# Sheet1.net
KiCad netlist of a schematic drawn in Altium Designer
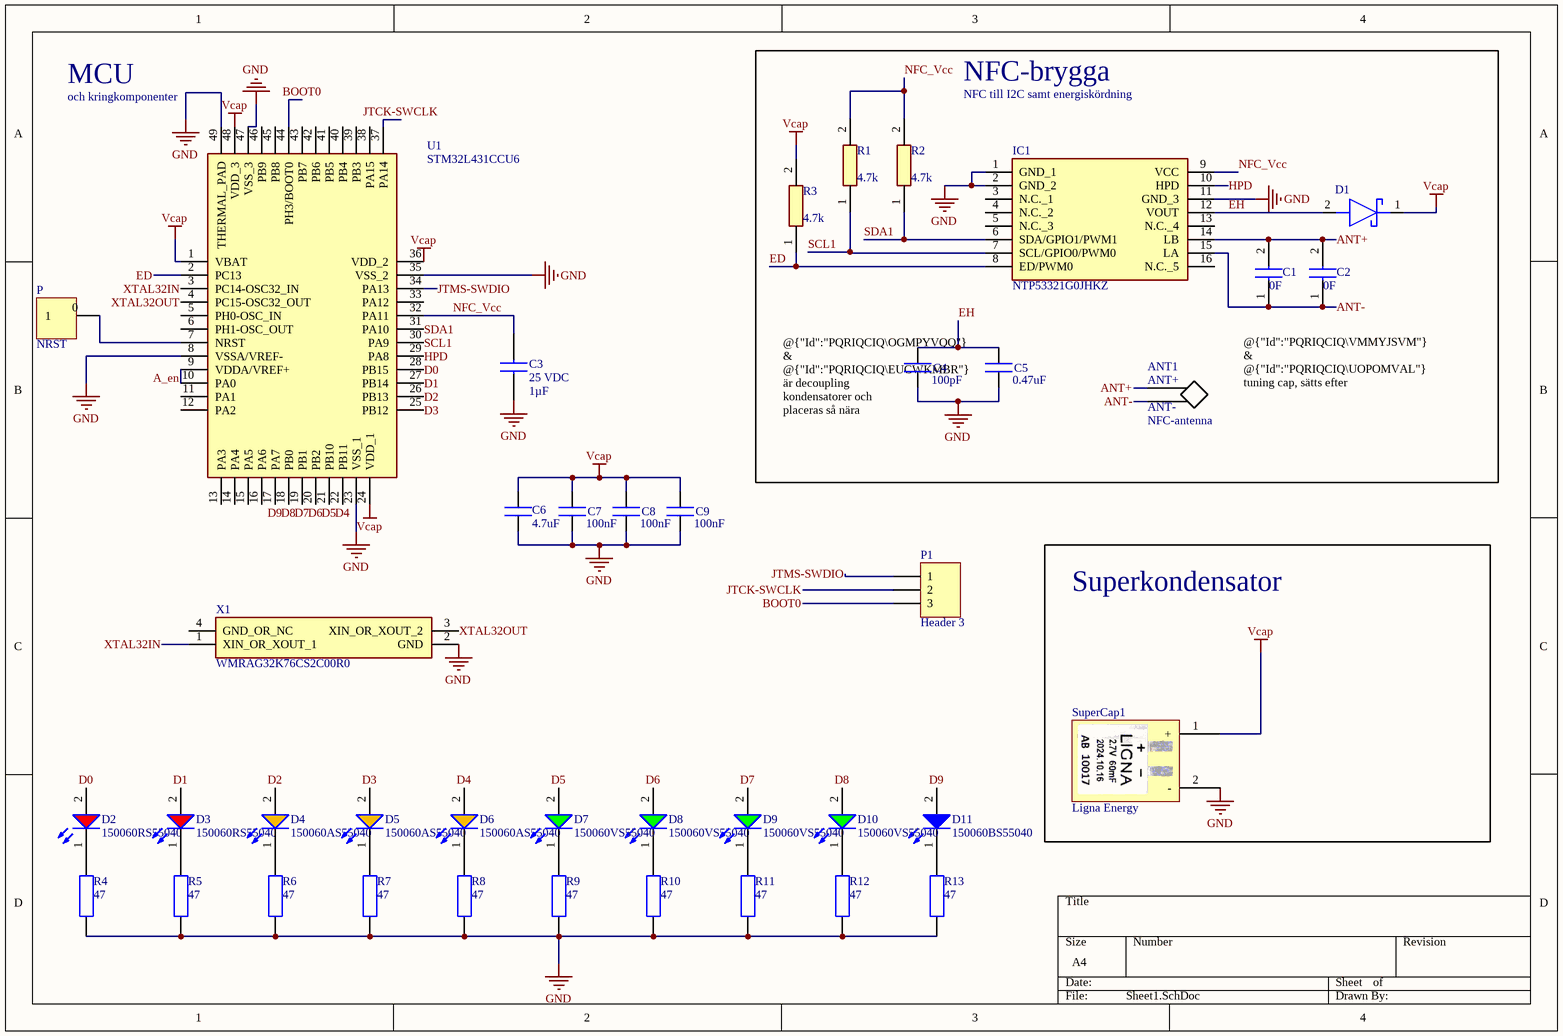
[diagram p0: Sheet1.SchDoc]

(export (version "E")
  (design (tool "Eeschema 10.0.6"))
  (components
    (comp (ref "ANT1")
      (value "NFC-antenna")
      (footprint "antenna3")
      (libsource (lib "Schlib") (part "NFC-antenna"))
    )
    (comp (ref "C1")
      (value "0F")
      (footprint "CAPC1005X70N")
      (description "Multilayer Ceramic Capacitors MLCC - SMD/SMT")
      (fields
        (field (name "MOUSER PART NUMBER") "81-GRM155C81C474KE1D")
        (field (name "MANUFACTURER_PART_NUMBER") "GRM155C81C474KE01D")
      )
      (libsource (lib "Linköpings Universitet (SE)") (part "GRM155C81C474KE01D"))
    )
    (comp (ref "C2")
      (value "0F")
      (footprint "CAPC1005X70N")
      (description "Multilayer Ceramic Capacitors MLCC - SMD/SMT")
      (fields
        (field (name "MOUSER PART NUMBER") "81-GRM155C81C474KE1D")
        (field (name "MANUFACTURER_PART_NUMBER") "GRM155C81C474KE01D")
      )
      (libsource (lib "Linköpings Universitet (SE)") (part "GRM155C81C474KE01D"))
    )
    (comp (ref "C3")
      (value "1µF")
      (footprint "CAPC1005X55N")
      (description "Capacitor")
      (fields
        (field (name "RATED VOLTAGE") "25 VDC")
        (field (name "MOUSER PART NUMBER") "81-GRM155R61E105KA2D")
        (field (name "ARROW PART NUMBER") "GRM155R61E105KA12D")
      )
      (libsource (lib "Linköpings Universitet (SE)") (part "GRM155R61E105KA12D"))
    )
    (comp (ref "C4")
      (value "C0402C101KCGACAUTO")
      (footprint "CAPC1005X70N")
      (description "Multilayer Ceramic Capacitors MLCC - SMD/SMT 500V 0.0001uF C0G 0402 10% AEC-Q200")
      (fields (field (name "CAPACITANCE") "100pF"))
      (libsource (lib "Schlib") (part "Generic capacitor"))
    )
    (comp (ref "C5")
      (value "C0402C101KCMBASJ105SB7474KFNA01GACAUTO")
      (footprint "CAPC1005X70N")
      (description "Multilayer Ceramic Capacitors MLCC - SMD/SMT 500V 0.0001uF C0G 0402 10% AEC-Q200")
      (fields (field (name "CAPACITANCE") "0.47uF"))
      (libsource (lib "Schlib") (part "Generic capacitor"))
    )
    (comp (ref "C6")
      (value "C0402C475K8PACTU")
      (footprint "CAPC1005X70N")
      (description "Multilayer Ceramic Capacitors MLCC - SMD/SMT")
      (fields (field (name "CAPACITANCE") "4.7uF"))
      (libsource (lib "Schlib") (part "Generic capacitor"))
    )
    (comp (ref "C7")
      (value "MLAST105SB5104KFNA01")
      (footprint "CAPC1005X70N")
      (description "Multilayer Ceramic Capacitors MLCC - SMD/SMT 25V 0.1uF X5R 0402 10% Medical")
      (fields (field (name "CAPACITANCE") "100nF"))
      (libsource (lib "Schlib") (part "Generic capacitor"))
    )
    (comp (ref "C8")
      (value "MLAST105SB5104KFNA01")
      (footprint "CAPC1005X70N")
      (description "Multilayer Ceramic Capacitors MLCC - SMD/SMT 25V 0.1uF X5R 0402 10% Medical")
      (fields (field (name "CAPACITANCE") "100nF"))
      (libsource (lib "Schlib") (part "Generic capacitor"))
    )
    (comp (ref "C9")
      (value "MLAST105SB5104KFNA01")
      (footprint "CAPC1005X70N")
      (description "Multilayer Ceramic Capacitors MLCC - SMD/SMT 25V 0.1uF X5R 0402 10% Medical")
      (fields (field (name "CAPACITANCE") "100nF"))
      (libsource (lib "Schlib") (part "Generic capacitor"))
    )
    (comp (ref "D1")
      (value "RBE01VYM6AFHTR")
      (footprint "RBE01VYM6AFHTR")
      (description "DIODE SCHOTTKY 6V 100MA TUMD2M")
      (fields (field (name "MOUSER PART NUMBER") "755-RBE01VYM6AFHTR"))
      (libsource (lib "Linköpings Universitet (SE)") (part "RBE01VYM6AFHTR"))
    )
    (comp (ref "D2")
      (value "150060RS55040")
      (footprint "WL-SMCD_0603")
      (description "LED RED DIFFUSED 0603 SMD")
      (libsource (lib "Altium Content Vault") (part "LED_Red_2A-1K"))
    )
    (comp (ref "D3")
      (value "150060RS55040")
      (footprint "WL-SMCD_0603")
      (description "LED RED DIFFUSED 0603 SMD")
      (libsource (lib "Altium Content Vault") (part "LED_Red_2A-1K"))
    )
    (comp (ref "D4")
      (value "150060AS55040")
      (footprint "WL-SMCD_0603")
      (description "150060AS55040 WL-SMCD SMT Mono-color Chip LED Diffused")
      (libsource (lib "Altium Content Vault") (part "LED_Amber_2A-1K"))
    )
    (comp (ref "D5")
      (value "150060AS55040")
      (footprint "WL-SMCD_0603")
      (description "150060AS55040 WL-SMCD SMT Mono-color Chip LED Diffused")
      (libsource (lib "Altium Content Vault") (part "LED_Amber_2A-1K"))
    )
    (comp (ref "D6")
      (value "150060AS55040")
      (footprint "WL-SMCD_0603")
      (description "150060AS55040 WL-SMCD SMT Mono-color Chip LED Diffused")
      (libsource (lib "Altium Content Vault") (part "LED_Amber_2A-1K"))
    )
    (comp (ref "D7")
      (value "150060VS55040")
      (footprint "WL-SMCD_0603")
      (description "150060VS55040 WL-SMCD SMT Mono-color Chip LED Diffused")
      (libsource (lib "Altium Content Vault") (part "LED_Green_2A-1K"))
    )
    (comp (ref "D8")
      (value "150060VS55040")
      (footprint "WL-SMCD_0603")
      (description "150060VS55040 WL-SMCD SMT Mono-color Chip LED Diffused")
      (libsource (lib "Altium Content Vault") (part "LED_Green_2A-1K"))
    )
    (comp (ref "D9")
      (value "150060VS55040")
      (footprint "WL-SMCD_0603")
      (description "150060VS55040 WL-SMCD SMT Mono-color Chip LED Diffused")
      (libsource (lib "Altium Content Vault") (part "LED_Green_2A-1K"))
    )
    (comp (ref "D10")
      (value "150060VS55040")
      (footprint "WL-SMCD_0603")
      (description "150060VS55040 WL-SMCD SMT Mono-color Chip LED Diffused")
      (libsource (lib "Altium Content Vault") (part "LED_Green_2A-1K"))
    )
    (comp (ref "D11")
      (value "150060BS55040")
      (footprint "WL-SMCD_0603")
      (description "150060BS55040 WL-SMCD SMT Mono-color Chip LED Diffused")
      (libsource (lib "Altium Content Vault") (part "LED_Blue_2A-1K"))
    )
    (comp (ref "IC1")
      (value "NTP53321G0JHKZ")
      (footprint "NTP53321G0JHKZ")
      (description "Interface - Specialized NTAG")
      (fields (field (name "MOUSER PART NUMBER") "771-NTP53321G0JHKZ"))
      (libsource (lib "Linköpings Universitet (SE)") (part "NTP53321G0JHKZ"))
    )
    (comp (ref "P")
      (value "NRST")
      (footprint "Testupoint")
      (libsource (lib "Schlib") (part "testpointu desu"))
    )
    (comp (ref "P1")
      (value "Header 3")
      (footprint "HDR1X3")
      (description "Header, 3-Pin")
      (fields (field (name "PUBLISHER") "Altium Limited"))
      (libsource (lib "Linköpings Universitet (SE)") (part "Header 3H"))
    )
    (comp (ref "R1")
      (value "CRCW04024K70FKEDHP")
      (footprint "RESC1005X40N")
      (fields (field (name "MOUSER PART NUMBER") "71-CRCW04024K70FKEDH") (field (name "RESISTANCE") "4.7k"))
      (libsource (lib "Linköpings Universitet (SE)") (part "CRCW04024K70FKEDHP"))
    )
    (comp (ref "R2")
      (value "CRCW04024K70FKEDHP")
      (footprint "RESC1005X40N")
      (fields (field (name "MOUSER PART NUMBER") "71-CRCW04024K70FKEDH") (field (name "RESISTANCE") "4.7k"))
      (libsource (lib "Linköpings Universitet (SE)") (part "CRCW04024K70FKEDHP"))
    )
    (comp (ref "R3")
      (value "CRCW04024K70FKEDHP")
      (footprint "RESC1005X40N")
      (fields (field (name "MOUSER PART NUMBER") "71-CRCW04024K70FKEDH") (field (name "RESISTANCE") "4.7k"))
      (libsource (lib "Linköpings Universitet (SE)") (part "CRCW04024K70FKEDHP"))
    )
    (comp (ref "R4")
      (value "SFR01MZPJ470")
      (footprint "RESC1005X40N")
      (description "Thick Film Resistors Sulfur Tolerant Chip Resistors 0402 case size")
      (fields (field (name "RESISTANCE") "47"))
      (libsource (lib "") (part "Generic resistor_1"))
    )
    (comp (ref "R5")
      (value "SFR01MZPJ470")
      (footprint "RESC1005X40N")
      (description "Thick Film Resistors Sulfur Tolerant Chip Resistors 0402 case size")
      (fields (field (name "RESISTANCE") "47"))
      (libsource (lib "") (part "Generic resistor_1"))
    )
    (comp (ref "R6")
      (value "SFR01MZPJ470")
      (footprint "RESC1005X40N")
      (description "Thick Film Resistors Sulfur Tolerant Chip Resistors 0402 case size")
      (fields (field (name "RESISTANCE") "47"))
      (libsource (lib "Schlib") (part "Generic resistor"))
    )
    (comp (ref "R7")
      (value "SFR01MZPJ470")
      (footprint "RESC1005X40N")
      (description "Thick Film Resistors Sulfur Tolerant Chip Resistors 0402 case size")
      (fields (field (name "RESISTANCE") "47"))
      (libsource (lib "Schlib") (part "Generic resistor"))
    )
    (comp (ref "R8")
      (value "SFR01MZPJ470")
      (footprint "RESC1005X40N")
      (description "Thick Film Resistors Sulfur Tolerant Chip Resistors 0402 case size")
      (fields (field (name "RESISTANCE") "47"))
      (libsource (lib "Schlib") (part "Generic resistor"))
    )
    (comp (ref "R9")
      (value "SFR01MZPJ470")
      (footprint "RESC1005X40N")
      (description "Thick Film Resistors Sulfur Tolerant Chip Resistors 0402 case size")
      (fields (field (name "RESISTANCE") "47"))
      (libsource (lib "Schlib") (part "Generic resistor"))
    )
    (comp (ref "R10")
      (value "SFR01MZPJ470")
      (footprint "RESC1005X40N")
      (description "Thick Film Resistors Sulfur Tolerant Chip Resistors 0402 case size")
      (fields (field (name "RESISTANCE") "47"))
      (libsource (lib "Schlib") (part "Generic resistor"))
    )
    (comp (ref "R11")
      (value "SFR01MZPJ470")
      (footprint "RESC1005X40N")
      (description "Thick Film Resistors Sulfur Tolerant Chip Resistors 0402 case size")
      (fields (field (name "RESISTANCE") "47"))
      (libsource (lib "Schlib") (part "Generic resistor"))
    )
    (comp (ref "R12")
      (value "SFR01MZPJ470")
      (footprint "RESC1005X40N")
      (description "Thick Film Resistors Sulfur Tolerant Chip Resistors 0402 case size")
      (fields (field (name "RESISTANCE") "47"))
      (libsource (lib "Schlib") (part "Generic resistor"))
    )
    (comp (ref "R13")
      (value "SFR01MZPJ470")
      (footprint "RESC1005X40N")
      (description "Thick Film Resistors Sulfur Tolerant Chip Resistors 0402 case size")
      (fields (field (name "RESISTANCE") "47"))
      (libsource (lib "Schlib") (part "Generic resistor"))
    )
    (comp (ref "SuperCap1")
      (value "Ligna Energy")
      (footprint "S-Power 2R slim")
      (libsource (lib "Schlib") (part "S-Power 2R"))
    )
    (comp (ref "U1")
      (value "STM32L431CCU6")
      (footprint "QFN50P700X700X60-49N-D")
      (description "ARM Microcontrollers - MCU 16/32-BITS MICROS")
      (fields (field (name "MOUSER PART NUMBER") "511-STM32L431CCU6"))
      (libsource (lib "Linköpings Universitet (SE)") (part "STM32L431CCU6"))
    )
    (comp (ref "X1")
      (value "WMRAG32K76CS2C00R0")
      (footprint "WMRAG32K76CS2C00R0")
      (description "32.768 kHz +/-20ppm Crystal 8pF 75 kOhms 4-SMD")
      (fields (field (name "MOUSER PART NUMBER") "81-WMRAG32K76CS2C00R"))
      (libsource (lib "Linköpings Universitet (SE)") (part "WMRAG32K76CS2C00R0"))
    )
  )
  (nets
    (net (code "1") (name "/ANT+") (class "Default")
      (node (ref "ANT1") (pin "1") (pinfunction "+_1") (pintype "passive"))
      (node (ref "C1") (pin "2") (pinfunction "2_2") (pintype "passive"))
      (node (ref "C2") (pin "2") (pinfunction "2_2") (pintype "passive"))
      (node (ref "IC1") (pin "14") (pinfunction "LB_14") (pintype "passive"))
    )
    (net (code "2") (name "/ANT-") (class "Default")
      (node (ref "ANT1") (pin "1") (pinfunction "-_1") (pintype "passive"))
      (node (ref "C1") (pin "1") (pinfunction "1_1") (pintype "passive"))
      (node (ref "C2") (pin "1") (pinfunction "1_1") (pintype "passive"))
      (node (ref "IC1") (pin "15") (pinfunction "LA_15") (pintype "passive"))
    )
    (net (code "3") (name "/A_en") (class "Default")
      (node (ref "U1") (pin "10") (pinfunction "PA0_10") (pintype "passive"))
      (node (ref "U1") (pin "9") (pinfunction "VDDA/VREF+_9") (pintype "passive"))
    )
    (net (code "4") (name "/BOOT0") (class "Default")
      (node (ref "P1") (pin "3") (pinfunction "3_3") (pintype "passive"))
      (node (ref "U1") (pin "44") (pinfunction "PH3/BOOT0_44") (pintype "passive"))
    )
    (net (code "5") (name "/D0") (class "Default")
      (node (ref "D2") (pin "2") (pinfunction "A_2") (pintype "passive"))
      (node (ref "U1") (pin "28") (pinfunction "PB15_28") (pintype "passive"))
    )
    (net (code "6") (name "/D1") (class "Default")
      (node (ref "D3") (pin "2") (pinfunction "A_2") (pintype "passive"))
      (node (ref "U1") (pin "27") (pinfunction "PB14_27") (pintype "passive"))
    )
    (net (code "7") (name "/D2") (class "Default")
      (node (ref "D4") (pin "2") (pinfunction "A_2") (pintype "passive"))
      (node (ref "U1") (pin "26") (pinfunction "PB13_26") (pintype "passive"))
    )
    (net (code "8") (name "/D3") (class "Default")
      (node (ref "D5") (pin "2") (pinfunction "A_2") (pintype "passive"))
      (node (ref "U1") (pin "25") (pinfunction "PB12_25") (pintype "passive"))
    )
    (net (code "9") (name "/D4") (class "Default")
      (node (ref "D6") (pin "2") (pinfunction "A_2") (pintype "passive"))
      (node (ref "U1") (pin "22") (pinfunction "PB11_22") (pintype "passive"))
    )
    (net (code "10") (name "/D5") (class "Default")
      (node (ref "D7") (pin "2") (pinfunction "A_2") (pintype "passive"))
      (node (ref "U1") (pin "21") (pinfunction "PB10_21") (pintype "passive"))
    )
    (net (code "11") (name "/D6") (class "Default")
      (node (ref "D8") (pin "2") (pinfunction "A_2") (pintype "passive"))
      (node (ref "U1") (pin "20") (pinfunction "PB2_20") (pintype "passive"))
    )
    (net (code "12") (name "/D7") (class "Default")
      (node (ref "D9") (pin "2") (pinfunction "A_2") (pintype "passive"))
      (node (ref "U1") (pin "19") (pinfunction "PB1_19") (pintype "passive"))
    )
    (net (code "13") (name "/D8") (class "Default")
      (node (ref "D10") (pin "2") (pinfunction "A_2") (pintype "passive"))
      (node (ref "U1") (pin "18") (pinfunction "PB0_18") (pintype "passive"))
    )
    (net (code "14") (name "/D9") (class "Default")
      (node (ref "D11") (pin "2") (pinfunction "A_2") (pintype "passive"))
      (node (ref "U1") (pin "17") (pinfunction "PA7_17") (pintype "passive"))
    )
    (net (code "15") (name "/ED") (class "Default")
      (node (ref "IC1") (pin "8") (pinfunction "ED/PWM0_8") (pintype "passive"))
      (node (ref "R3") (pin "1") (pinfunction "1_1") (pintype "passive"))
      (node (ref "U1") (pin "2") (pinfunction "PC13_2") (pintype "passive"))
    )
    (net (code "16") (name "/EH") (class "Default")
      (node (ref "C4") (pin "2") (pinfunction "2_2") (pintype "passive"))
      (node (ref "C5") (pin "2") (pinfunction "2_2") (pintype "passive"))
      (node (ref "D1") (pin "2") (pinfunction "A_2") (pintype "passive"))
      (node (ref "IC1") (pin "12") (pinfunction "VOUT_12") (pintype "passive"))
    )
    (net (code "17") (name "/HPD") (class "Default")
      (node (ref "IC1") (pin "10") (pinfunction "HPD_10") (pintype "passive"))
      (node (ref "U1") (pin "29") (pinfunction "PA8_29") (pintype "passive"))
    )
    (net (code "18") (name "/JTCK-SWCLK") (class "Default")
      (node (ref "P1") (pin "2") (pinfunction "2_2") (pintype "passive"))
      (node (ref "U1") (pin "37") (pinfunction "PA14_37") (pintype "passive"))
    )
    (net (code "19") (name "/JTMS-SWDIO") (class "Default")
      (node (ref "P1") (pin "1") (pinfunction "1_1") (pintype "passive"))
      (node (ref "U1") (pin "34") (pinfunction "PA13_34") (pintype "passive"))
    )
    (net (code "20") (name "/NFC_Vcc") (class "Default")
      (node (ref "C3") (pin "1") (pinfunction "1_1") (pintype "passive"))
      (node (ref "IC1") (pin "9") (pinfunction "VCC_9") (pintype "passive"))
      (node (ref "R1") (pin "2") (pinfunction "2_2") (pintype "passive"))
      (node (ref "R2") (pin "2") (pinfunction "2_2") (pintype "passive"))
      (node (ref "U1") (pin "32") (pinfunction "PA11_32") (pintype "passive"))
    )
    (net (code "21") (name "/SCL1") (class "Default")
      (node (ref "IC1") (pin "7") (pinfunction "SCL/GPIO0/PWM0_7") (pintype "passive"))
      (node (ref "R1") (pin "1") (pinfunction "1_1") (pintype "passive"))
      (node (ref "U1") (pin "30") (pinfunction "PA9_30") (pintype "passive"))
    )
    (net (code "22") (name "/SDA1") (class "Default")
      (node (ref "IC1") (pin "6") (pinfunction "SDA/GPIO1/PWM1_6") (pintype "passive"))
      (node (ref "R2") (pin "1") (pinfunction "1_1") (pintype "passive"))
      (node (ref "U1") (pin "31") (pinfunction "PA10_31") (pintype "passive"))
    )
    (net (code "23") (name "/XTAL32IN") (class "Default")
      (node (ref "U1") (pin "3") (pinfunction "PC14-OSC32_IN_3") (pintype "passive"))
      (node (ref "X1") (pin "1") (pinfunction "XIN_OR_XOUT_1_1") (pintype "passive"))
    )
    (net (code "24") (name "/XTAL32OUT") (class "Default")
      (node (ref "U1") (pin "4") (pinfunction "PC15-OSC32_OUT_4") (pintype "passive"))
      (node (ref "X1") (pin "3") (pinfunction "XIN_OR_XOUT_2_3") (pintype "passive"))
    )
    (net (code "25") (name "GND") (class "Default")
      (node (ref "C3") (pin "2") (pinfunction "2_2") (pintype "passive"))
      (node (ref "C4") (pin "1") (pinfunction "1_1") (pintype "passive"))
      (node (ref "C5") (pin "1") (pinfunction "1_1") (pintype "passive"))
      (node (ref "C6") (pin "2") (pinfunction "2_2") (pintype "passive"))
      (node (ref "C7") (pin "2") (pinfunction "2_2") (pintype "passive"))
      (node (ref "C8") (pin "2") (pinfunction "2_2") (pintype "passive"))
      (node (ref "C9") (pin "2") (pinfunction "2_2") (pintype "passive"))
      (node (ref "IC1") (pin "1") (pinfunction "GND_1_1") (pintype "passive"))
      (node (ref "IC1") (pin "11") (pinfunction "GND_3_11") (pintype "passive"))
      (node (ref "IC1") (pin "2") (pinfunction "GND_2_2") (pintype "passive"))
      (node (ref "R10") (pin "2") (pinfunction "2_2") (pintype "passive"))
      (node (ref "R11") (pin "2") (pinfunction "2_2") (pintype "passive"))
      (node (ref "R12") (pin "2") (pinfunction "2_2") (pintype "passive"))
      (node (ref "R13") (pin "2") (pinfunction "2_2") (pintype "passive"))
      (node (ref "R4") (pin "1") (pinfunction "1_1") (pintype "passive"))
      (node (ref "R5") (pin "1") (pinfunction "1_1") (pintype "passive"))
      (node (ref "R6") (pin "2") (pinfunction "2_2") (pintype "passive"))
      (node (ref "R7") (pin "2") (pinfunction "2_2") (pintype "passive"))
      (node (ref "R8") (pin "2") (pinfunction "2_2") (pintype "passive"))
      (node (ref "R9") (pin "2") (pinfunction "2_2") (pintype "passive"))
      (node (ref "SuperCap1") (pin "2") (pinfunction "-_2") (pintype "passive"))
      (node (ref "U1") (pin "23") (pinfunction "VSS_1_23") (pintype "passive"))
      (node (ref "U1") (pin "35") (pinfunction "VSS_2_35") (pintype "passive"))
      (node (ref "U1") (pin "47") (pinfunction "VSS_3_47") (pintype "passive"))
      (node (ref "U1") (pin "49") (pinfunction "THERMAL_PAD_49") (pintype "passive"))
      (node (ref "U1") (pin "8") (pinfunction "VSSA/VREF-_8") (pintype "passive"))
      (node (ref "X1") (pin "2") (pinfunction "GND_2") (pintype "passive"))
    )
    (net (code "26") (name "Net-(D2-K)") (class "Default")
      (node (ref "D2") (pin "1") (pinfunction "K_1") (pintype "passive"))
      (node (ref "R4") (pin "2") (pinfunction "2_2") (pintype "passive"))
    )
    (net (code "27") (name "Net-(D3-K)") (class "Default")
      (node (ref "D3") (pin "1") (pinfunction "K_1") (pintype "passive"))
      (node (ref "R5") (pin "2") (pinfunction "2_2") (pintype "passive"))
    )
    (net (code "28") (name "Net-(D4-K)") (class "Default")
      (node (ref "D4") (pin "1") (pinfunction "K_1") (pintype "passive"))
      (node (ref "R6") (pin "1") (pinfunction "1_1") (pintype "passive"))
    )
    (net (code "29") (name "Net-(D5-K)") (class "Default")
      (node (ref "D5") (pin "1") (pinfunction "K_1") (pintype "passive"))
      (node (ref "R7") (pin "1") (pinfunction "1_1") (pintype "passive"))
    )
    (net (code "30") (name "Net-(D6-K)") (class "Default")
      (node (ref "D6") (pin "1") (pinfunction "K_1") (pintype "passive"))
      (node (ref "R8") (pin "1") (pinfunction "1_1") (pintype "passive"))
    )
    (net (code "31") (name "Net-(D7-K)") (class "Default")
      (node (ref "D7") (pin "1") (pinfunction "K_1") (pintype "passive"))
      (node (ref "R9") (pin "1") (pinfunction "1_1") (pintype "passive"))
    )
    (net (code "32") (name "Net-(D8-K)") (class "Default")
      (node (ref "D8") (pin "1") (pinfunction "K_1") (pintype "passive"))
      (node (ref "R10") (pin "1") (pinfunction "1_1") (pintype "passive"))
    )
    (net (code "33") (name "Net-(D9-K)") (class "Default")
      (node (ref "D9") (pin "1") (pinfunction "K_1") (pintype "passive"))
      (node (ref "R11") (pin "1") (pinfunction "1_1") (pintype "passive"))
    )
    (net (code "34") (name "Net-(D10-K)") (class "Default")
      (node (ref "D10") (pin "1") (pinfunction "K_1") (pintype "passive"))
      (node (ref "R12") (pin "1") (pinfunction "1_1") (pintype "passive"))
    )
    (net (code "35") (name "Net-(D11-K)") (class "Default")
      (node (ref "D11") (pin "1") (pinfunction "K_1") (pintype "passive"))
      (node (ref "R13") (pin "1") (pinfunction "1_1") (pintype "passive"))
    )
    (net (code "36") (name "Net-(P-1)") (class "Default")
      (node (ref "P") (pin "0") (pinfunction "1_0") (pintype "passive"))
      (node (ref "U1") (pin "7") (pinfunction "NRST_7") (pintype "passive"))
    )
    (net (code "37") (name "Vcap") (class "Default")
      (node (ref "C6") (pin "1") (pinfunction "1_1") (pintype "passive"))
      (node (ref "C7") (pin "1") (pinfunction "1_1") (pintype "passive"))
      (node (ref "C8") (pin "1") (pinfunction "1_1") (pintype "passive"))
      (node (ref "C9") (pin "1") (pinfunction "1_1") (pintype "passive"))
      (node (ref "D1") (pin "1") (pinfunction "K_1") (pintype "passive"))
      (node (ref "R3") (pin "2") (pinfunction "2_2") (pintype "passive"))
      (node (ref "SuperCap1") (pin "1") (pinfunction "+_1") (pintype "passive"))
      (node (ref "U1") (pin "1") (pinfunction "VBAT_1") (pintype "passive"))
      (node (ref "U1") (pin "24") (pinfunction "VDD_1_24") (pintype "passive"))
      (node (ref "U1") (pin "36") (pinfunction "VDD_2_36") (pintype "passive"))
      (node (ref "U1") (pin "48") (pinfunction "VDD_3_48") (pintype "passive"))
    )
    (net (code "38") (name "unconnected-(IC1-N.C._1-Pad3)") (class "Default")
      (node (ref "IC1") (pin "3") (pinfunction "N.C._1_3") (pintype "passive"))
    )
    (net (code "39") (name "unconnected-(IC1-N.C._2-Pad4)") (class "Default")
      (node (ref "IC1") (pin "4") (pinfunction "N.C._2_4") (pintype "passive"))
    )
    (net (code "40") (name "unconnected-(IC1-N.C._3-Pad5)") (class "Default")
      (node (ref "IC1") (pin "5") (pinfunction "N.C._3_5") (pintype "passive"))
    )
    (net (code "41") (name "unconnected-(IC1-N.C._4-Pad13)") (class "Default")
      (node (ref "IC1") (pin "13") (pinfunction "N.C._4_13") (pintype "passive"))
    )
    (net (code "42") (name "unconnected-(IC1-N.C._5-Pad16)") (class "Default")
      (node (ref "IC1") (pin "16") (pinfunction "N.C._5_16") (pintype "passive"))
    )
    (net (code "43") (name "unconnected-(U1-PA1-Pad11)") (class "Default")
      (node (ref "U1") (pin "11") (pinfunction "PA1_11") (pintype "passive"))
    )
    (net (code "44") (name "unconnected-(U1-PA2-Pad12)") (class "Default")
      (node (ref "U1") (pin "12") (pinfunction "PA2_12") (pintype "passive"))
    )
    (net (code "45") (name "unconnected-(U1-PA3-Pad13)") (class "Default")
      (node (ref "U1") (pin "13") (pinfunction "PA3_13") (pintype "passive"))
    )
    (net (code "46") (name "unconnected-(U1-PA4-Pad14)") (class "Default")
      (node (ref "U1") (pin "14") (pinfunction "PA4_14") (pintype "passive"))
    )
    (net (code "47") (name "unconnected-(U1-PA5-Pad15)") (class "Default")
      (node (ref "U1") (pin "15") (pinfunction "PA5_15") (pintype "passive"))
    )
    (net (code "48") (name "unconnected-(U1-PA6-Pad16)") (class "Default")
      (node (ref "U1") (pin "16") (pinfunction "PA6_16") (pintype "passive"))
    )
    (net (code "49") (name "unconnected-(U1-PA12-Pad33)") (class "Default")
      (node (ref "U1") (pin "33") (pinfunction "PA12_33") (pintype "passive"))
    )
    (net (code "50") (name "unconnected-(U1-PA15-Pad38)") (class "Default")
      (node (ref "U1") (pin "38") (pinfunction "PA15_38") (pintype "passive"))
    )
    (net (code "51") (name "unconnected-(U1-PB3-Pad39)") (class "Default")
      (node (ref "U1") (pin "39") (pinfunction "PB3_39") (pintype "passive"))
    )
    (net (code "52") (name "unconnected-(U1-PB4-Pad40)") (class "Default")
      (node (ref "U1") (pin "40") (pinfunction "PB4_40") (pintype "passive"))
    )
    (net (code "53") (name "unconnected-(U1-PB5-Pad41)") (class "Default")
      (node (ref "U1") (pin "41") (pinfunction "PB5_41") (pintype "passive"))
    )
    (net (code "54") (name "unconnected-(U1-PB6-Pad42)") (class "Default")
      (node (ref "U1") (pin "42") (pinfunction "PB6_42") (pintype "passive"))
    )
    (net (code "55") (name "unconnected-(U1-PB7-Pad43)") (class "Default")
      (node (ref "U1") (pin "43") (pinfunction "PB7_43") (pintype "passive"))
    )
    (net (code "56") (name "unconnected-(U1-PB8-Pad45)") (class "Default")
      (node (ref "U1") (pin "45") (pinfunction "PB8_45") (pintype "passive"))
    )
    (net (code "57") (name "unconnected-(U1-PB9-Pad46)") (class "Default")
      (node (ref "U1") (pin "46") (pinfunction "PB9_46") (pintype "passive"))
    )
    (net (code "58") (name "unconnected-(U1-PH0-OSC_IN-Pad5)") (class "Default")
      (node (ref "U1") (pin "5") (pinfunction "PH0-OSC_IN_5") (pintype "passive"))
    )
    (net (code "59") (name "unconnected-(U1-PH1-OSC_OUT-Pad6)") (class "Default")
      (node (ref "U1") (pin "6") (pinfunction "PH1-OSC_OUT_6") (pintype "passive"))
    )
    (net (code "60") (name "unconnected-(X1-GND_OR_NC-Pad4)") (class "Default")
      (node (ref "X1") (pin "4") (pinfunction "GND_OR_NC_4") (pintype "passive"))
    )
  )
)
